# POWER.net
KiCad netlist of a schematic drawn in Altium Designer
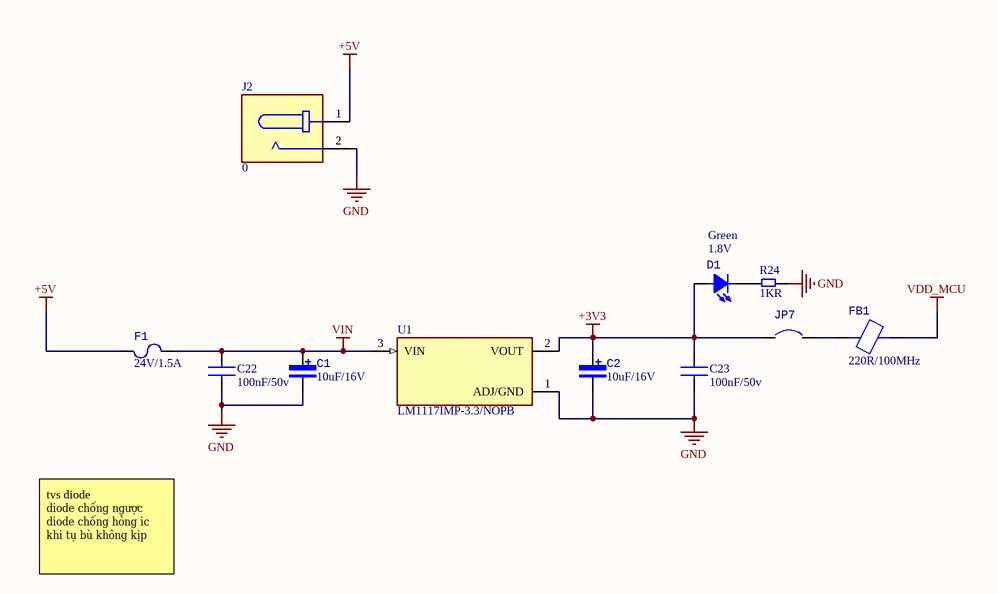
[diagram p0: POWER.SchDoc]

(export (version "E")
  (design (tool "Eeschema 10.0.6"))
  (components
    (comp (ref "C1")
      (value "10uF/16V")
      (footprint "CAP_Tantalum_3216")
      (description "Tụ Tantalum 10uF 16V 1206 TAJA106K016RNJ")
      (libsource (lib "Database_Libs1") (part "CAP-TAN"))
    )
    (comp (ref "C2")
      (value "10uF/16V")
      (footprint "CAP_Tantalum_3216")
      (description "Tụ Tantalum 10uF 16V 1206 TAJA106K016RNJ")
      (libsource (lib "Database_Libs1") (part "CAP-TAN"))
    )
    (comp (ref "C22") (value "100nF/50v") (footprint "CAP-CER-0805") (libsource (lib "ID") (part "CAP-CER")))
    (comp (ref "C23") (value "100nF/50v") (footprint "CAP-CER-0805") (libsource (lib "ID") (part "CAP-CER")))
    (comp (ref "D1")
      (value "1.8V")
      (footprint "LED_SMD_0805_GREEN")
      (description "LED Xanh Lá 0805 Dán SMD Trong Suốt Harvatek")
      (fields (field (name "MFR# #") "Green"))
      (libsource (lib "Database_Libs1") (part "LED"))
    )
    (comp (ref "F1")
      (value "24V/1.5A")
      (footprint "FUSER_MF-MSMF150/24X-2")
      (description "MF-MSMF150/24X-2 Cầu Chì Tự Phục Hồi 1812 24V 1.5A")
      (libsource (lib "Database_Libs1") (part "FUSE"))
    )
    (comp (ref "FB1")
      (value "220R/100MHz")
      (footprint "FERRITE-0603")
      (libsource (lib "Database_Libs1") (part "FERRITE-BEAD"))
    )
    (comp (ref "J2")
      (value "0")
      (footprint "CUI_PJ-037AH")
      (description "2.0 x 6.5 mm, 5.0 A, Horizontal, Through Hole, Dc Power Jack Connector")
      (fields (field (name "MF") "Same Sky") (field (name "MP") "PJ-037AH"))
      (libsource (lib "ID") (part "JACK DC"))
    )
    (comp (ref "JP7")
      (value "JUMPER-2POS")
      (footprint "JUMPER-2POS-2.54")
      (libsource (lib "Database_Libs1") (part "JUMPER-2POS"))
    )
    (comp (ref "R24") (value "1KR") (footprint "RES-SMD-0805") (libsource (lib "ID") (part "RES_SMD")))
    (comp (ref "U1")
      (value "LM1117IMP-3.3/NOPB")
      (footprint "LM1117IMP-3.3/NOPB")
      (description "800-mA 15-V linear voltage regulator")
      (fields (field (name "MF") "Texas Instruments"))
      (libsource (lib "ID") (part "LDO"))
    )
  )
  (nets
    (net (code "1") (name "+3V3") (class "Default")
      (node (ref "C2") (pin "1") (pinfunction "1_1") (pintype "passive"))
      (node (ref "C23") (pin "2") (pinfunction "2_2") (pintype "passive"))
      (node (ref "D1") (pin "1") (pinfunction "A_1") (pintype "passive"))
      (node (ref "JP7") (pin "1") (pinfunction "1_1") (pintype "passive"))
      (node (ref "U1") (pin "2") (pinfunction "VOUT_2") (pintype "power_in"))
    )
    (net (code "2") (name "+5V") (class "Default")
      (node (ref "F1") (pin "2") (pinfunction "2_2") (pintype "passive"))
      (node (ref "J2") (pin "1") (pinfunction "1_1") (pintype "passive"))
    )
    (net (code "3") (name "GND") (class "Default")
      (node (ref "C1") (pin "2") (pinfunction "2_2") (pintype "passive"))
      (node (ref "C2") (pin "2") (pinfunction "2_2") (pintype "passive"))
      (node (ref "C22") (pin "1") (pinfunction "1_1") (pintype "passive"))
      (node (ref "C23") (pin "1") (pinfunction "1_1") (pintype "passive"))
      (node (ref "J2") (pin "2") (pinfunction "2_2") (pintype "power_in"))
      (node (ref "R24") (pin "2") (pinfunction "2_2") (pintype "passive"))
      (node (ref "U1") (pin "1") (pinfunction "ADJ/GND_1") (pintype "power_in"))
    )
    (net (code "4") (name "Net-(D1-K)") (class "Default")
      (node (ref "D1") (pin "2") (pinfunction "K_2") (pintype "passive"))
      (node (ref "R24") (pin "1") (pinfunction "1_1") (pintype "passive"))
    )
    (net (code "5") (name "Net-(FB1-Pad1)") (class "Default")
      (node (ref "FB1") (pin "1") (pinfunction "1_1") (pintype "passive"))
      (node (ref "JP7") (pin "2") (pinfunction "2_2") (pintype "passive"))
    )
    (net (code "6") (name "VDD_MCU") (class "Default")
      (node (ref "FB1") (pin "2") (pinfunction "2_2") (pintype "passive"))
    )
    (net (code "7") (name "VIN") (class "Default")
      (node (ref "C1") (pin "1") (pinfunction "1_1") (pintype "passive"))
      (node (ref "C22") (pin "2") (pinfunction "2_2") (pintype "passive"))
      (node (ref "F1") (pin "1") (pinfunction "1_1") (pintype "passive"))
      (node (ref "U1") (pin "3") (pinfunction "VIN_3") (pintype "input"))
    )
  )
)
